# RV-3032-C7_RTC.net
KiCad netlist of a schematic drawn in Altium Designer
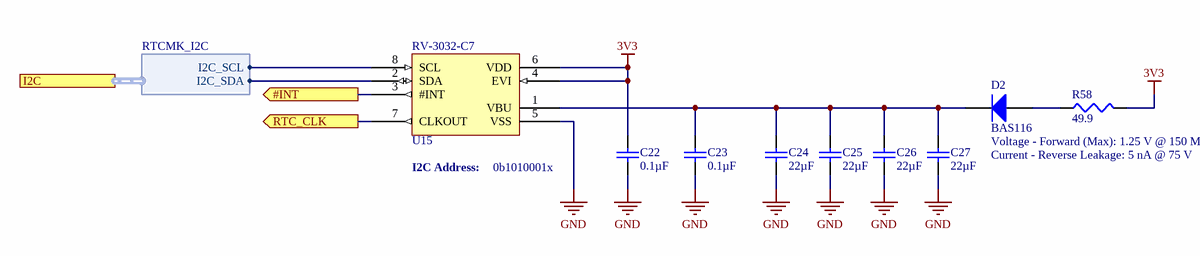
[diagram p0: RV-3032-C7 RTC.SchDoc]

(export (version "E")
  (design (tool "Eeschema 10.0.6"))
  (components
    (comp (ref "C22")
      (value "0.1µF")
      (footprint "TDK-CGA2B")
      (description "CAP CER 0.1UF 50V X7R 0402")
      (fields
        (field (name "PART NUMBER") "PC-TDK-02259")
        (field (name "MANUFACTURER PART NUMBER") "CGA2B3X7R1H104K050BB")
        (field (name "PUBLISHER") "AlbertaSat")
      )
      (libsource (lib "Database") (part "Cap"))
    )
    (comp (ref "C23")
      (value "0.1µF")
      (footprint "TDK-CGA2B")
      (description "CAP CER 0.1UF 50V X7R 0402")
      (fields
        (field (name "PART NUMBER") "PC-TDK-02259")
        (field (name "MANUFACTURER PART NUMBER") "CGA2B3X7R1H104K050BB")
        (field (name "PUBLISHER") "AlbertaSat")
      )
      (libsource (lib "Database") (part "Cap"))
    )
    (comp (ref "C24")
      (value "22µF")
      (footprint "TY-1206L")
      (description "CAP CER 22UF 16V X7R 1206")
      (fields
        (field (name "PART NUMBER") "PC-TY-00721")
        (field (name "MANUFACTURER PART NUMBER") "EMK316BB7226ML-T")
        (field (name "PUBLISHER") "AlbertaSat")
      )
      (libsource (lib "Database") (part "Cap"))
    )
    (comp (ref "C25")
      (value "22µF")
      (footprint "TY-1206L")
      (description "CAP CER 22UF 16V X7R 1206")
      (fields
        (field (name "PART NUMBER") "PC-TY-00721")
        (field (name "MANUFACTURER PART NUMBER") "EMK316BB7226ML-T")
        (field (name "PUBLISHER") "AlbertaSat")
      )
      (libsource (lib "Database") (part "Cap"))
    )
    (comp (ref "C26")
      (value "22µF")
      (footprint "TY-1206L")
      (description "CAP CER 22UF 16V X7R 1206")
      (fields
        (field (name "PART NUMBER") "PC-TY-00721")
        (field (name "MANUFACTURER PART NUMBER") "EMK316BB7226ML-T")
        (field (name "PUBLISHER") "AlbertaSat")
      )
      (libsource (lib "Database") (part "Cap"))
    )
    (comp (ref "C27")
      (value "22µF")
      (footprint "TY-1206L")
      (description "CAP CER 22UF 16V X7R 1206")
      (fields
        (field (name "PART NUMBER") "PC-TY-00721")
        (field (name "MANUFACTURER PART NUMBER") "EMK316BB7226ML-T")
        (field (name "PUBLISHER") "AlbertaSat")
      )
      (libsource (lib "Database") (part "Cap"))
    )
    (comp (ref "D2")
      (value "BAS116")
      (footprint "DIOD-DFN1006-2")
      (description "DIODE GEN PURP 85V 215MA 2DFN")
      (fields
        (field (name "PART NUMBER") "61")
        (field (name "MANUFACTURER PART NUMBER") "BAS116LPH4-7B")
        (field (name "VOLTAGE - FORWARD (MAX)") "1.25 V @ 150 Ma")
        (field (name "CURRENT - REVERSE LEAKAGE") "5 nA @ 75 V")
        (field (name "PUBLISHER") "Altium Limited")
      )
      (libsource (lib "Database") (part "Diode"))
    )
    (comp (ref "R58")
      (value "49.9")
      (footprint "PANA-ERJ2R")
      (description "RES SMD 49.9 OHM 1% 1/10W 0402")
      (fields
        (field (name "PART NUMBER") "13732")
        (field (name "MANUFACTURER PART NUMBER") "ERJ-2RKF49R9X")
        (field (name "PUBLISHER") "Altium Limited")
      )
      (libsource (lib "Database") (part "Res3"))
    )
    (comp (ref "U15")
      (value "RV-3032-C7")
      (footprint "MCS-RV-3032-C7")
      (description "Real Time Clock (RTC) IC Clock/Calendar 16B, 32B I²C, 2-Wire Serial 8-WCDFN")
      (fields
        (field (name "PART NUMBER") "PU-MCS-00001")
        (field (name "MANUFACTURER PART NUMBER") "RV-3032-C7 32.768kHz-2.5PPM-TA-QA")
        (field (name "PUBLISHER") "AlbertaSat")
      )
      (libsource (lib "Database") (part "RV-3032-C7"))
    )
  )
  (nets
    (net (code "2") (name "/#INT") (class "Default")
      (node (ref "U15") (pin "3") (pinfunction "#INT_3") (pintype "output"))
    )
    (net (code "3") (name "/I2C_SCL") (class "Default")
      (node (ref "U15") (pin "8") (pinfunction "SCL_8") (pintype "input"))
    )
    (net (code "4") (name "/I2C_SDA") (class "Default")
      (node (ref "U15") (pin "2") (pinfunction "SDA_2") (pintype "bidirectional"))
    )
    (net (code "5") (name "/RTC_CLK") (class "Default")
      (node (ref "U15") (pin "7") (pinfunction "CLKOUT_7") (pintype "output"))
    )
    (net (code "7") (name "3V3") (class "Default")
      (node (ref "C22") (pin "1") (pinfunction "1_1") (pintype "passive"))
      (node (ref "R58") (pin "2") (pinfunction "2_2") (pintype "passive"))
      (node (ref "U15") (pin "4") (pinfunction "EVI_4") (pintype "input"))
      (node (ref "U15") (pin "6") (pinfunction "VDD_6") (pintype "power_in"))
    )
    (net (code "8") (name "GND") (class "Default")
      (node (ref "C22") (pin "2") (pinfunction "2_2") (pintype "passive"))
      (node (ref "C23") (pin "2") (pinfunction "2_2") (pintype "passive"))
      (node (ref "C24") (pin "1") (pinfunction "1_1") (pintype "passive"))
      (node (ref "C25") (pin "1") (pinfunction "1_1") (pintype "passive"))
      (node (ref "C26") (pin "1") (pinfunction "1_1") (pintype "passive"))
      (node (ref "C27") (pin "1") (pinfunction "1_1") (pintype "passive"))
      (node (ref "U15") (pin "5") (pinfunction "VSS_5") (pintype "power_in"))
    )
    (net (code "9") (name "Net-(D2-A)") (class "Default")
      (node (ref "D2") (pin "1") (pinfunction "A_1") (pintype "passive"))
      (node (ref "R58") (pin "1") (pinfunction "1_1") (pintype "passive"))
    )
    (net (code "10") (name "Net-(D2-K)") (class "Default")
      (node (ref "C23") (pin "1") (pinfunction "1_1") (pintype "passive"))
      (node (ref "C24") (pin "2") (pinfunction "2_2") (pintype "passive"))
      (node (ref "C25") (pin "2") (pinfunction "2_2") (pintype "passive"))
      (node (ref "C26") (pin "2") (pinfunction "2_2") (pintype "passive"))
      (node (ref "C27") (pin "2") (pinfunction "2_2") (pintype "passive"))
      (node (ref "D2") (pin "2") (pinfunction "K_2") (pintype "passive"))
      (node (ref "U15") (pin "1") (pinfunction "VBU_1") (pintype "power_in"))
    )
  )
)
